# vl6180x.net
KiCad netlist of a schematic drawn in EAGLE
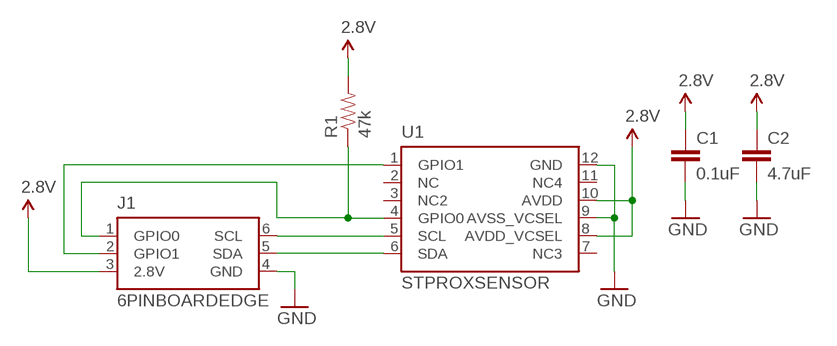
[diagram p0: schematic, sheet 1]

(export (version "E")
  (design (tool "Eeschema 10.0.6"))
  (components
    (comp (ref "C1")
      (value "0.1uF")
      (footprint "eagle-import:0603-CAP")
      (libsource (lib "eagle-import") (part "CAP0603-CAP"))
    )
    (comp (ref "C2")
      (value "4.7uF")
      (footprint "eagle-import:0603-CAP")
      (libsource (lib "eagle-import") (part "CAP0603-CAP"))
    )
    (comp (ref "J1")
      (value "6PINBOARDEDGE")
      (footprint "eagle-import:6PINBOARDEDGE")
      (libsource (lib "eagle-import") (part "6PINBOARDEDGE"))
    )
    (comp (ref "R1")
      (value "47k")
      (footprint "eagle-import:0603-RES")
      (libsource (lib "eagle-import") (part "RESISTOR0603-RES"))
    )
    (comp (ref "U1")
      (value "STPROXSENSOR")
      (footprint "eagle-import:STPROXSENSOR")
      (libsource (lib "eagle-import") (part "STPROXSENSOR"))
    )
  )
  (nets
    (net (code "1") (name "2.8V") (class "Default")
      (node (ref "C1") (pin "1") (pinfunction "1_1") (pintype "passive"))
      (node (ref "C2") (pin "1") (pinfunction "1_1") (pintype "passive"))
      (node (ref "J1") (pin "3") (pinfunction "2.8V_3") (pintype "bidirectional"))
      (node (ref "R1") (pin "2") (pinfunction "2_2") (pintype "passive"))
      (node (ref "U1") (pin "10") (pinfunction "AVDD_10") (pintype "bidirectional"))
      (node (ref "U1") (pin "8") (pinfunction "AVDD_VCSEL_8") (pintype "bidirectional"))
    )
    (net (code "2") (name "GND") (class "Default")
      (node (ref "C1") (pin "2") (pinfunction "2_2") (pintype "passive"))
      (node (ref "C2") (pin "2") (pinfunction "2_2") (pintype "passive"))
      (node (ref "J1") (pin "4") (pinfunction "GND_4") (pintype "bidirectional"))
      (node (ref "U1") (pin "12") (pinfunction "GND_12") (pintype "bidirectional"))
      (node (ref "U1") (pin "9") (pinfunction "AVSS_VCSEL_9") (pintype "bidirectional"))
    )
    (net (code "3") (name "Net-(J1-GPIO0)") (class "Default")
      (node (ref "J1") (pin "1") (pinfunction "GPIO0_1") (pintype "bidirectional"))
      (node (ref "R1") (pin "1") (pinfunction "1_1") (pintype "passive"))
      (node (ref "U1") (pin "4") (pinfunction "GPIO0_4") (pintype "bidirectional"))
    )
    (net (code "4") (name "Net-(J1-GPIO1)") (class "Default")
      (node (ref "J1") (pin "2") (pinfunction "GPIO1_2") (pintype "bidirectional"))
      (node (ref "U1") (pin "1") (pinfunction "GPIO1_1") (pintype "bidirectional"))
    )
    (net (code "5") (name "Net-(J1-SCL)") (class "Default")
      (node (ref "J1") (pin "6") (pinfunction "SCL_6") (pintype "bidirectional"))
      (node (ref "U1") (pin "5") (pinfunction "SCL_5") (pintype "bidirectional"))
    )
    (net (code "6") (name "Net-(J1-SDA)") (class "Default")
      (node (ref "J1") (pin "5") (pinfunction "SDA_5") (pintype "bidirectional"))
      (node (ref "U1") (pin "6") (pinfunction "SDA_6") (pintype "bidirectional"))
    )
    (net (code "7") (name "unconnected-(U1-NC-Pad2)") (class "Default")
      (node (ref "U1") (pin "2") (pinfunction "NC_2") (pintype "bidirectional"))
    )
    (net (code "8") (name "unconnected-(U1-NC2-Pad3)") (class "Default")
      (node (ref "U1") (pin "3") (pinfunction "NC2_3") (pintype "bidirectional"))
    )
    (net (code "9") (name "unconnected-(U1-NC3-Pad7)") (class "Default")
      (node (ref "U1") (pin "7") (pinfunction "NC3_7") (pintype "bidirectional"))
    )
    (net (code "10") (name "unconnected-(U1-NC4-Pad11)") (class "Default")
      (node (ref "U1") (pin "11") (pinfunction "NC4_11") (pintype "bidirectional"))
    )
  )
)
